# Adafruit_UDA1334_I2S_DAC.net
KiCad netlist of a schematic drawn in EAGLE
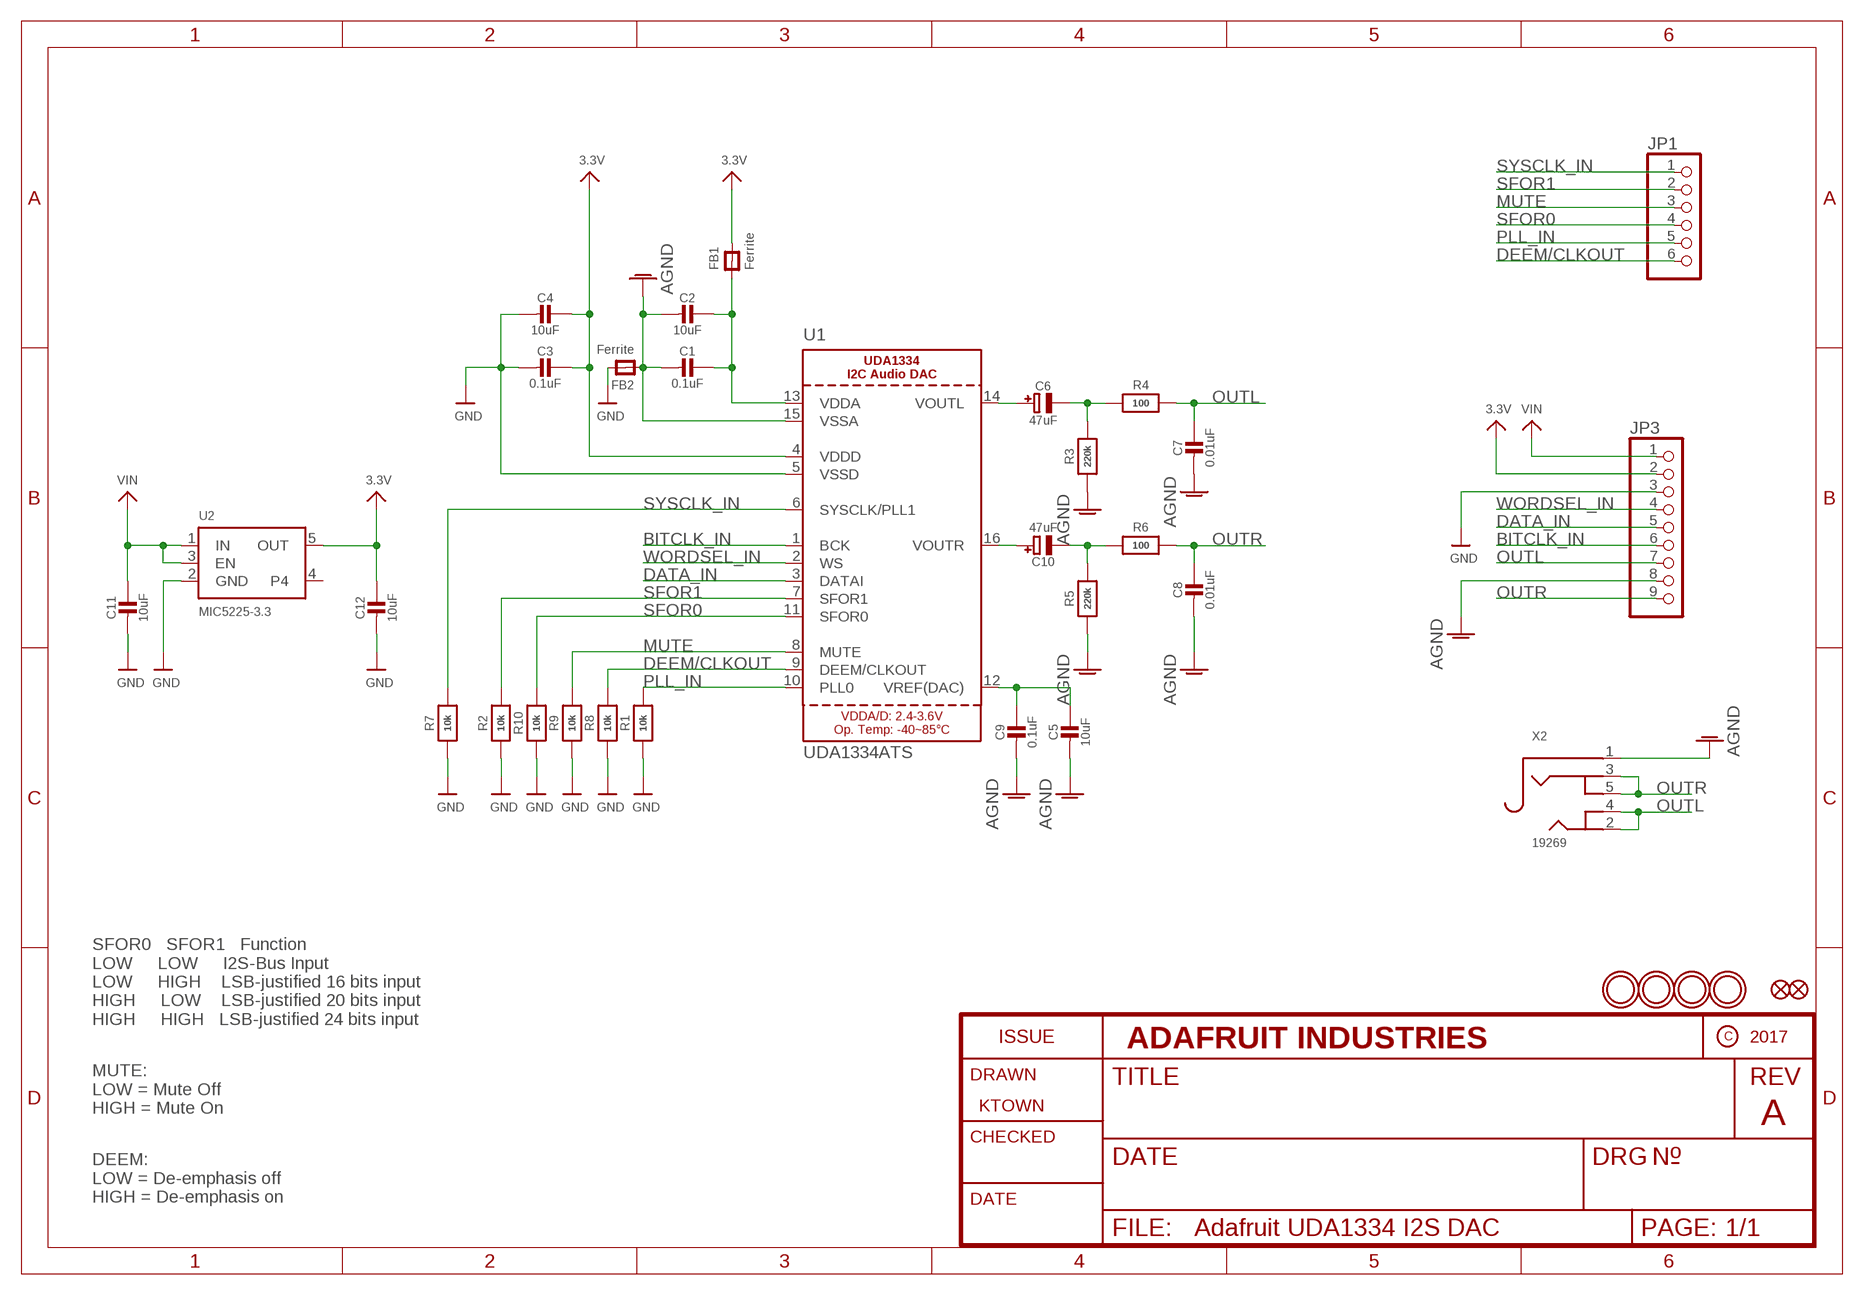
[diagram p0: schematic, sheet 1]

(export (version "E")
  (design (tool "Eeschema 10.0.6"))
  (components
    (comp (ref "C1")
      (value "0.1uF")
      (footprint "eagle-import:0805-NO")
      (libsource (lib "eagle-import") (part "CAP_CERAMIC0805-NOOUTLINE"))
    )
    (comp (ref "C2")
      (value "10uF")
      (footprint "eagle-import:0805-NO")
      (libsource (lib "eagle-import") (part "CAP_CERAMIC0805-NOOUTLINE"))
    )
    (comp (ref "C3")
      (value "0.1uF")
      (footprint "eagle-import:0805-NO")
      (libsource (lib "eagle-import") (part "CAP_CERAMIC0805-NOOUTLINE"))
    )
    (comp (ref "C4")
      (value "10uF")
      (footprint "eagle-import:0805-NO")
      (libsource (lib "eagle-import") (part "CAP_CERAMIC0805-NOOUTLINE"))
    )
    (comp (ref "C5")
      (value "10uF")
      (footprint "eagle-import:0805-NO")
      (libsource (lib "eagle-import") (part "CAP_CERAMIC0805-NOOUTLINE"))
    )
    (comp (ref "C6")
      (value "47uF")
      (footprint "eagle-import:PANASONIC_C")
      (libsource (lib "eagle-import") (part "CAP_ELECTROLYTICPANASONIC_C"))
    )
    (comp (ref "C7")
      (value "0.01uF")
      (footprint "eagle-import:0805-NO")
      (libsource (lib "eagle-import") (part "CAP_CERAMIC0805-NOOUTLINE"))
    )
    (comp (ref "C8")
      (value "0.01uF")
      (footprint "eagle-import:0805-NO")
      (libsource (lib "eagle-import") (part "CAP_CERAMIC0805-NOOUTLINE"))
    )
    (comp (ref "C9")
      (value "0.1uF")
      (footprint "eagle-import:0805-NO")
      (libsource (lib "eagle-import") (part "CAP_CERAMIC0805-NOOUTLINE"))
    )
    (comp (ref "C10")
      (value "47uF")
      (footprint "eagle-import:PANASONIC_C")
      (libsource (lib "eagle-import") (part "CAP_ELECTROLYTICPANASONIC_C"))
    )
    (comp (ref "C11")
      (value "10uF")
      (footprint "eagle-import:0805-NO")
      (libsource (lib "eagle-import") (part "CAP_CERAMIC0805-NOOUTLINE"))
    )
    (comp (ref "C12")
      (value "10uF")
      (footprint "eagle-import:0805-NO")
      (libsource (lib "eagle-import") (part "CAP_CERAMIC0805-NOOUTLINE"))
    )
    (comp (ref "FB1")
      (value "Ferrite")
      (footprint "eagle-import:0805")
      (libsource (lib "eagle-import") (part "FERRITE0805"))
    )
    (comp (ref "FB2")
      (value "Ferrite")
      (footprint "eagle-import:0805")
      (libsource (lib "eagle-import") (part "FERRITE0805"))
    )
    (comp (ref "FID1")
      (value "FIDUCIAL_1MM")
      (footprint "eagle-import:FIDUCIAL_1MM")
      (libsource (lib "eagle-import") (part "FIDUCIAL_1MM"))
    )
    (comp (ref "FID2")
      (value "FIDUCIAL_1MM")
      (footprint "eagle-import:FIDUCIAL_1MM")
      (libsource (lib "eagle-import") (part "FIDUCIAL_1MM"))
    )
    (comp (ref "JP1")
      (value "HEADER-1X670MIL")
      (footprint "eagle-import:1X06_ROUND_70")
      (libsource (lib "eagle-import") (part "HEADER-1X670MIL"))
    )
    (comp (ref "JP3")
      (value "HEADER-1X970MIL")
      (footprint "eagle-import:1X09_ROUND_70")
      (libsource (lib "eagle-import") (part "HEADER-1X970MIL"))
    )
    (comp (ref "R1")
      (value "10k")
      (footprint "eagle-import:0603-NO")
      (libsource (lib "eagle-import") (part "RESISTOR_0603_NOOUT"))
    )
    (comp (ref "R2")
      (value "10k")
      (footprint "eagle-import:0603-NO")
      (libsource (lib "eagle-import") (part "RESISTOR_0603_NOOUT"))
    )
    (comp (ref "R3")
      (value "220k")
      (footprint "eagle-import:0805-NO")
      (libsource (lib "eagle-import") (part "RESISTOR0805_NOOUTLINE"))
    )
    (comp (ref "R4")
      (value "100")
      (footprint "eagle-import:0805-NO")
      (libsource (lib "eagle-import") (part "RESISTOR0805_NOOUTLINE"))
    )
    (comp (ref "R5")
      (value "220k")
      (footprint "eagle-import:0805-NO")
      (libsource (lib "eagle-import") (part "RESISTOR0805_NOOUTLINE"))
    )
    (comp (ref "R6")
      (value "100")
      (footprint "eagle-import:0805-NO")
      (libsource (lib "eagle-import") (part "RESISTOR0805_NOOUTLINE"))
    )
    (comp (ref "R7")
      (value "10k")
      (footprint "eagle-import:0603-NO")
      (libsource (lib "eagle-import") (part "RESISTOR_0603_NOOUT"))
    )
    (comp (ref "R8")
      (value "10k")
      (footprint "eagle-import:0603-NO")
      (libsource (lib "eagle-import") (part "RESISTOR_0603_NOOUT"))
    )
    (comp (ref "R9")
      (value "10k")
      (footprint "eagle-import:0603-NO")
      (libsource (lib "eagle-import") (part "RESISTOR_0603_NOOUT"))
    )
    (comp (ref "R10")
      (value "10k")
      (footprint "eagle-import:0603-NO")
      (libsource (lib "eagle-import") (part "RESISTOR_0603_NOOUT"))
    )
    (comp (ref "U$11")
      (value "MOUNTINGHOLE2.5")
      (footprint "eagle-import:MOUNTINGHOLE_2.5_PLATED")
      (libsource (lib "eagle-import") (part "MOUNTINGHOLE2.5"))
    )
    (comp (ref "U$12")
      (value "MOUNTINGHOLE2.5")
      (footprint "eagle-import:MOUNTINGHOLE_2.5_PLATED")
      (libsource (lib "eagle-import") (part "MOUNTINGHOLE2.5"))
    )
    (comp (ref "U$13")
      (value "MOUNTINGHOLE2.5")
      (footprint "eagle-import:MOUNTINGHOLE_2.5_PLATED")
      (libsource (lib "eagle-import") (part "MOUNTINGHOLE2.5"))
    )
    (comp (ref "U$14")
      (value "MOUNTINGHOLE2.5")
      (footprint "eagle-import:MOUNTINGHOLE_2.5_PLATED")
      (libsource (lib "eagle-import") (part "MOUNTINGHOLE2.5"))
    )
    (comp (ref "U1")
      (value "UDA1334ATS")
      (footprint "eagle-import:SSOP16_4.4MM")
      (libsource (lib "eagle-import") (part "AUDIO_I2S_UDA1334{dblquote}{dblquote}"))
    )
    (comp (ref "U2")
      (value "MIC5225-3.3")
      (footprint "eagle-import:SOT23-5")
      (libsource (lib "eagle-import") (part "VREG_SOT23-5"))
    )
    (comp (ref "X2")
      (value "19269")
      (footprint "eagle-import:4UCONN_19269")
      (libsource (lib "eagle-import") (part "AUDIO_3.5MMJACK"))
    )
  )
  (nets
    (net (code "1") (name "/BITCLK_IN") (class "Default")
      (node (ref "JP3") (pin "6") (pinfunction "6_6") (pintype "passive"))
      (node (ref "U1") (pin "1") (pinfunction "BCK_1") (pintype "input"))
    )
    (net (code "2") (name "/DATA_IN") (class "Default")
      (node (ref "JP3") (pin "5") (pinfunction "5_5") (pintype "passive"))
      (node (ref "U1") (pin "3") (pinfunction "DATAI_3") (pintype "input"))
    )
    (net (code "3") (name "/DEEM{slash}CLKOUT") (class "Default")
      (node (ref "JP1") (pin "6") (pinfunction "6_6") (pintype "passive"))
      (node (ref "R8") (pin "2") (pinfunction "2_2") (pintype "passive"))
      (node (ref "U1") (pin "9") (pinfunction "DEEM/CLKOUT_9") (pintype "bidirectional"))
    )
    (net (code "4") (name "/MUTE") (class "Default")
      (node (ref "JP1") (pin "3") (pinfunction "3_3") (pintype "passive"))
      (node (ref "R9") (pin "2") (pinfunction "2_2") (pintype "passive"))
      (node (ref "U1") (pin "8") (pinfunction "MUTE_8") (pintype "input"))
    )
    (net (code "5") (name "/OUTL") (class "Default")
      (node (ref "C7") (pin "1") (pinfunction "1_1") (pintype "passive"))
      (node (ref "JP3") (pin "7") (pinfunction "7_7") (pintype "passive"))
      (node (ref "R4") (pin "2") (pinfunction "2_2") (pintype "passive"))
      (node (ref "X2") (pin "2") (pinfunction "P$5_2") (pintype "bidirectional"))
      (node (ref "X2") (pin "4") (pinfunction "P$4_4") (pintype "bidirectional"))
    )
    (net (code "6") (name "/OUTR") (class "Default")
      (node (ref "C8") (pin "1") (pinfunction "1_1") (pintype "passive"))
      (node (ref "JP3") (pin "9") (pinfunction "9_9") (pintype "passive"))
      (node (ref "R6") (pin "2") (pinfunction "2_2") (pintype "passive"))
      (node (ref "X2") (pin "3") (pinfunction "P$2_3") (pintype "bidirectional"))
      (node (ref "X2") (pin "5") (pinfunction "P$3_5") (pintype "bidirectional"))
    )
    (net (code "7") (name "/PLL_IN") (class "Default")
      (node (ref "JP1") (pin "5") (pinfunction "5_5") (pintype "passive"))
      (node (ref "R1") (pin "2") (pinfunction "2_2") (pintype "passive"))
      (node (ref "U1") (pin "10") (pinfunction "PLL0_10") (pintype "input"))
    )
    (net (code "8") (name "/SFOR0") (class "Default")
      (node (ref "JP1") (pin "4") (pinfunction "4_4") (pintype "passive"))
      (node (ref "R10") (pin "2") (pinfunction "2_2") (pintype "passive"))
      (node (ref "U1") (pin "11") (pinfunction "SFOR0_11") (pintype "input"))
    )
    (net (code "9") (name "/SFOR1") (class "Default")
      (node (ref "JP1") (pin "2") (pinfunction "2_2") (pintype "passive"))
      (node (ref "R2") (pin "2") (pinfunction "2_2") (pintype "passive"))
      (node (ref "U1") (pin "7") (pinfunction "SFOR1_7") (pintype "input"))
    )
    (net (code "10") (name "/SYSCLK_IN") (class "Default")
      (node (ref "JP1") (pin "1") (pinfunction "1_1") (pintype "passive"))
      (node (ref "R7") (pin "2") (pinfunction "2_2") (pintype "passive"))
      (node (ref "U1") (pin "6") (pinfunction "SYSCLK/PLL1_6") (pintype "input"))
    )
    (net (code "11") (name "/WORDSEL_IN") (class "Default")
      (node (ref "JP3") (pin "4") (pinfunction "4_4") (pintype "passive"))
      (node (ref "U1") (pin "2") (pinfunction "WS_2") (pintype "input"))
    )
    (net (code "12") (name "3.3V") (class "Default")
      (node (ref "C12") (pin "1") (pinfunction "1_1") (pintype "passive"))
      (node (ref "C3") (pin "1") (pinfunction "1_1") (pintype "passive"))
      (node (ref "C4") (pin "1") (pinfunction "1_1") (pintype "passive"))
      (node (ref "FB1") (pin "2") (pinfunction "P$2_2") (pintype "passive"))
      (node (ref "JP3") (pin "2") (pinfunction "2_2") (pintype "passive"))
      (node (ref "U1") (pin "4") (pinfunction "VDDD_4") (pintype "power_in"))
      (node (ref "U2") (pin "5") (pinfunction "OUT_5") (pintype "power_in"))
    )
    (net (code "13") (name "AGND") (class "Default")
      (node (ref "C1") (pin "2") (pinfunction "2_2") (pintype "passive"))
      (node (ref "C2") (pin "2") (pinfunction "2_2") (pintype "passive"))
      (node (ref "C5") (pin "2") (pinfunction "2_2") (pintype "passive"))
      (node (ref "C7") (pin "2") (pinfunction "2_2") (pintype "passive"))
      (node (ref "C8") (pin "2") (pinfunction "2_2") (pintype "passive"))
      (node (ref "C9") (pin "2") (pinfunction "2_2") (pintype "passive"))
      (node (ref "FB2") (pin "1") (pinfunction "P$1_1") (pintype "passive"))
      (node (ref "JP3") (pin "8") (pinfunction "8_8") (pintype "passive"))
      (node (ref "R3") (pin "1") (pinfunction "1_1") (pintype "passive"))
      (node (ref "R5") (pin "1") (pinfunction "1_1") (pintype "passive"))
      (node (ref "U1") (pin "15") (pinfunction "VSSA_15") (pintype "power_in"))
      (node (ref "X2") (pin "1") (pinfunction "P$1_1") (pintype "bidirectional"))
    )
    (net (code "14") (name "GND") (class "Default")
      (node (ref "C11") (pin "2") (pinfunction "2_2") (pintype "passive"))
      (node (ref "C12") (pin "2") (pinfunction "2_2") (pintype "passive"))
      (node (ref "C3") (pin "2") (pinfunction "2_2") (pintype "passive"))
      (node (ref "C4") (pin "2") (pinfunction "2_2") (pintype "passive"))
      (node (ref "FB2") (pin "2") (pinfunction "P$2_2") (pintype "passive"))
      (node (ref "JP3") (pin "3") (pinfunction "3_3") (pintype "passive"))
      (node (ref "R1") (pin "1") (pinfunction "1_1") (pintype "passive"))
      (node (ref "R10") (pin "1") (pinfunction "1_1") (pintype "passive"))
      (node (ref "R2") (pin "1") (pinfunction "1_1") (pintype "passive"))
      (node (ref "R7") (pin "1") (pinfunction "1_1") (pintype "passive"))
      (node (ref "R8") (pin "1") (pinfunction "1_1") (pintype "passive"))
      (node (ref "R9") (pin "1") (pinfunction "1_1") (pintype "passive"))
      (node (ref "U1") (pin "5") (pinfunction "VSSD_5") (pintype "power_in"))
      (node (ref "U2") (pin "2") (pinfunction "GND_2") (pintype "power_in"))
    )
    (net (code "15") (name "Net-(C6-Pad-)") (class "Default")
      (node (ref "C6") (pin "-") (pinfunction "-_-") (pintype "passive"))
      (node (ref "R3") (pin "2") (pinfunction "2_2") (pintype "passive"))
      (node (ref "R4") (pin "1") (pinfunction "1_1") (pintype "passive"))
    )
    (net (code "16") (name "Net-(C10-Pad-)") (class "Default")
      (node (ref "C10") (pin "-") (pinfunction "-_-") (pintype "passive"))
      (node (ref "R5") (pin "2") (pinfunction "2_2") (pintype "passive"))
      (node (ref "R6") (pin "1") (pinfunction "1_1") (pintype "passive"))
    )
    (net (code "17") (name "Net-(FB1-P$1)") (class "Default")
      (node (ref "C1") (pin "1") (pinfunction "1_1") (pintype "passive"))
      (node (ref "C2") (pin "1") (pinfunction "1_1") (pintype "passive"))
      (node (ref "FB1") (pin "1") (pinfunction "P$1_1") (pintype "passive"))
      (node (ref "U1") (pin "13") (pinfunction "VDDA_13") (pintype "power_in"))
    )
    (net (code "18") (name "Net-(U1-VOUTL)") (class "Default")
      (node (ref "C6") (pin "+") (pinfunction "+_+") (pintype "passive"))
      (node (ref "U1") (pin "14") (pinfunction "VOUTL_14") (pintype "output"))
    )
    (net (code "19") (name "Net-(U1-VOUTR)") (class "Default")
      (node (ref "C10") (pin "+") (pinfunction "+_+") (pintype "passive"))
      (node (ref "U1") (pin "16") (pinfunction "VOUTR_16") (pintype "output"))
    )
    (net (code "20") (name "Net-(U1-VREF(DAC))") (class "Default")
      (node (ref "C5") (pin "1") (pinfunction "1_1") (pintype "passive"))
      (node (ref "C9") (pin "1") (pinfunction "1_1") (pintype "passive"))
      (node (ref "U1") (pin "12") (pinfunction "VREF(DAC)_12") (pintype "output"))
    )
    (net (code "21") (name "VIN") (class "Default")
      (node (ref "C11") (pin "1") (pinfunction "1_1") (pintype "passive"))
      (node (ref "JP3") (pin "1") (pinfunction "1_1") (pintype "passive"))
      (node (ref "U2") (pin "1") (pinfunction "IN_1") (pintype "power_in"))
      (node (ref "U2") (pin "3") (pinfunction "EN_3") (pintype "input"))
    )
    (net (code "22") (name "unconnected-(U2-P4-Pad4)") (class "Default")
      (node (ref "U2") (pin "4") (pinfunction "P4_4") (pintype "bidirectional"))
    )
  )
)
